# HelpDuinoShiledV1.net
KiCad netlist of a schematic drawn in EAGLE
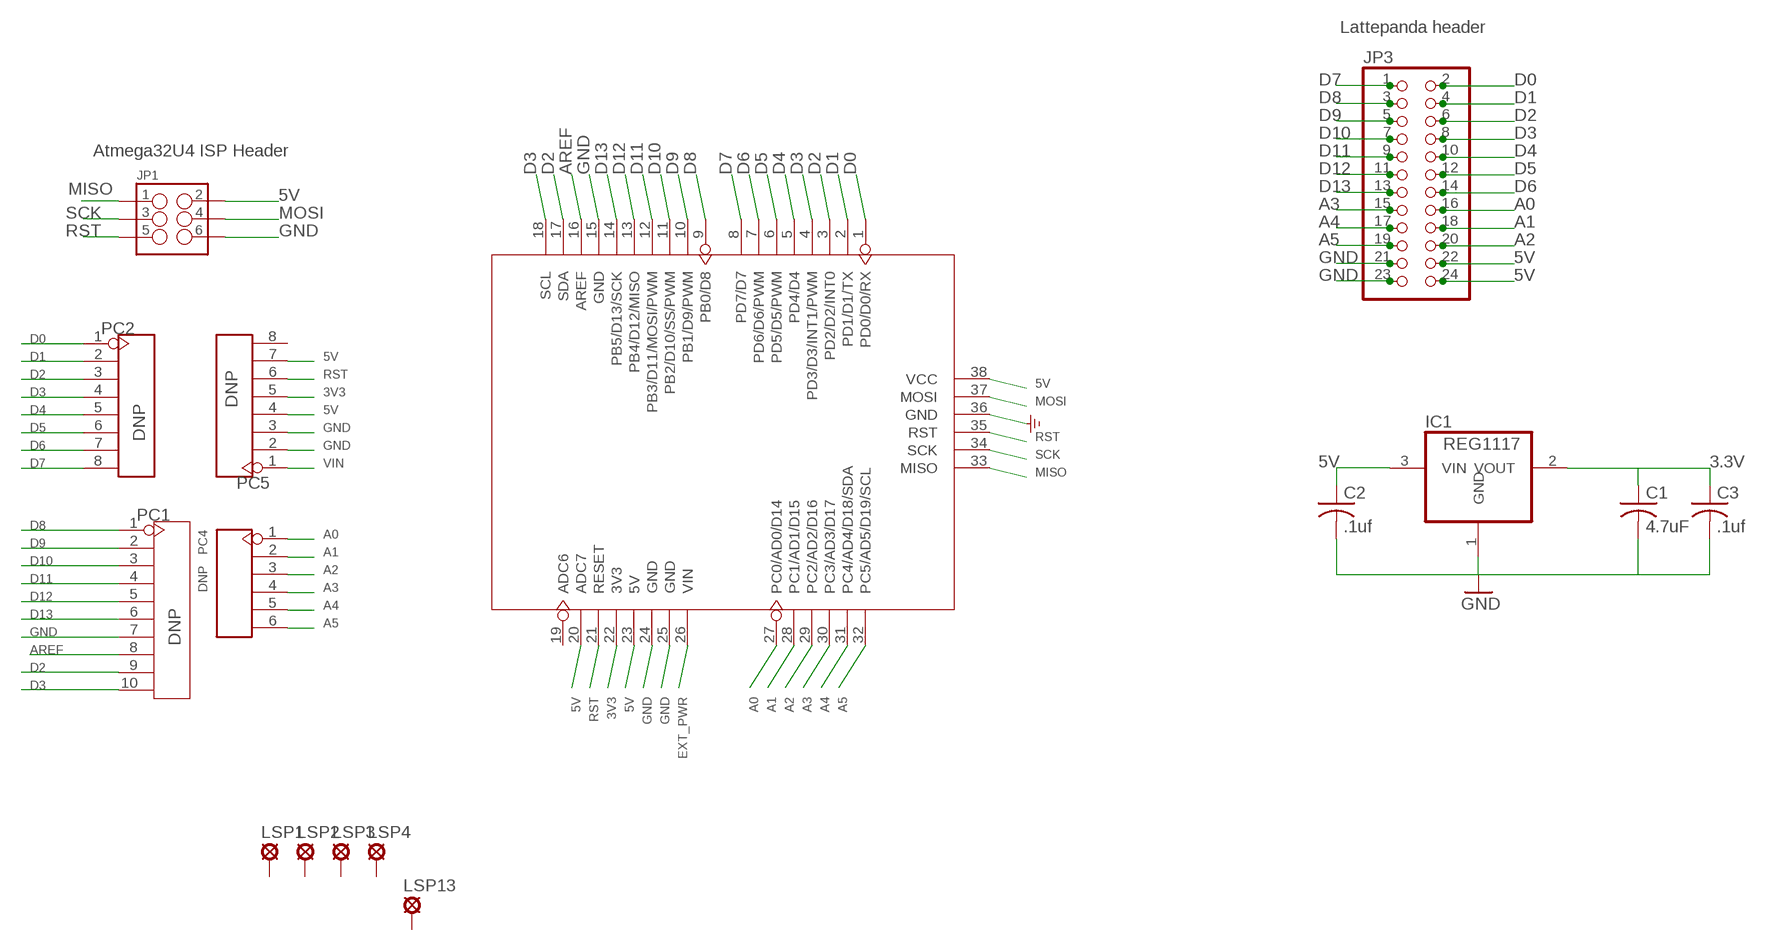
[diagram p0: schematic, sheet 1]

(export (version "E")
  (design (tool "Eeschema 10.0.6"))
  (components
    (comp (ref "C1")
      (value "4.7uF")
      (footprint "eagle-import:C0603K")
      (libsource (lib "eagle-import") (part "C-USC0603K"))
    )
    (comp (ref "C2")
      (value ".1uf")
      (footprint "eagle-import:C0603K")
      (libsource (lib "eagle-import") (part "C-USC0603K"))
    )
    (comp (ref "C3")
      (value ".1uf")
      (footprint "eagle-import:C0603K")
      (libsource (lib "eagle-import") (part "C-USC0603K"))
    )
    (comp (ref "IC1")
      (value "REG1117")
      (footprint "eagle-import:SOT223")
      (libsource (lib "eagle-import") (part "REG1117"))
    )
    (comp (ref "JP1")
      (value "M03X2NO_SILK")
      (footprint "eagle-import:2X3-NS")
      (libsource (lib "eagle-import") (part "M03X2NO_SILK"))
    )
    (comp (ref "JP3")
      (value "PINHD-2X12")
      (footprint "eagle-import:2X12")
      (libsource (lib "eagle-import") (part "PINHD-2X12"))
    )
    (comp (ref "LSP1")
      (value "SE13")
      (footprint "eagle-import:SE13")
      (libsource (lib "eagle-import") (part "SE13"))
    )
    (comp (ref "LSP2")
      (value "SE13")
      (footprint "eagle-import:SE13")
      (libsource (lib "eagle-import") (part "SE13"))
    )
    (comp (ref "LSP3")
      (value "SE13")
      (footprint "eagle-import:SE13")
      (libsource (lib "eagle-import") (part "SE13"))
    )
    (comp (ref "LSP4")
      (value "SE13")
      (footprint "eagle-import:SE13")
      (libsource (lib "eagle-import") (part "SE13"))
    )
    (comp (ref "LSP13")
      (value "SE13")
      (footprint "eagle-import:SE13")
      (libsource (lib "eagle-import") (part "SE13"))
    )
    (comp (ref "PC1")
      (value "DNP")
      (footprint "eagle-import:10P-2.54")
      (libsource (lib "eagle-import") (part "HEADER-10P-2.54"))
    )
    (comp (ref "PC2")
      (value "DNP")
      (footprint "eagle-import:8P-2.54")
      (libsource (lib "eagle-import") (part "HEADER-8P-2.54"))
    )
    (comp (ref "PC4")
      (value "DNP")
      (footprint "eagle-import:6P-2.54-65_35MIL")
      (libsource (lib "eagle-import") (part "HEADER-6P-65/35MIL"))
    )
    (comp (ref "PC5")
      (value "DNP")
      (footprint "eagle-import:8P-2.54")
      (libsource (lib "eagle-import") (part "HEADER-8P-2.54"))
    )
    (comp (ref "U1")
      (value "ARDUINO-38PWITH/-SILK")
      (footprint "eagle-import:ARDUINO-38P-WITH_-SILK-500519002")
      (libsource (lib "eagle-import") (part "ARDUINO-38PWITH/-SILK"))
    )
  )
  (nets
    (net (code "1") (name "/3.3V") (class "Default")
      (node (ref "C1") (pin "1") (pinfunction "1_1") (pintype "passive"))
      (node (ref "C3") (pin "1") (pinfunction "1_1") (pintype "passive"))
      (node (ref "IC1") (pin "2") (pinfunction "VOUT_2") (pintype "output"))
    )
    (net (code "2") (name "/3V3") (class "Default")
      (node (ref "PC5") (pin "5") (pinfunction "5_5") (pintype "bidirectional"))
      (node (ref "U1") (pin "22") (pinfunction "3V3_22") (pintype "bidirectional"))
    )
    (net (code "3") (name "/5V") (class "Default")
      (node (ref "C2") (pin "1") (pinfunction "1_1") (pintype "passive"))
      (node (ref "IC1") (pin "3") (pinfunction "VIN_3") (pintype "input"))
      (node (ref "JP1") (pin "2") (pinfunction "2_2") (pintype "bidirectional"))
      (node (ref "JP3") (pin "22") (pinfunction "22_22") (pintype "passive"))
      (node (ref "JP3") (pin "24") (pinfunction "24_24") (pintype "passive"))
      (node (ref "PC5") (pin "4") (pinfunction "4_4") (pintype "bidirectional"))
      (node (ref "PC5") (pin "7") (pinfunction "7_7") (pintype "bidirectional"))
      (node (ref "U1") (pin "20") (pinfunction "ADC7_20") (pintype "bidirectional"))
      (node (ref "U1") (pin "23") (pinfunction "5V_23") (pintype "bidirectional"))
      (node (ref "U1") (pin "38") (pinfunction "VCC_38") (pintype "bidirectional"))
    )
    (net (code "4") (name "/A0") (class "Default")
      (node (ref "JP3") (pin "16") (pinfunction "16_16") (pintype "passive"))
      (node (ref "PC4") (pin "1") (pinfunction "1_1") (pintype "bidirectional"))
      (node (ref "U1") (pin "27") (pinfunction "PC0/AD0/D14_27") (pintype "bidirectional"))
    )
    (net (code "5") (name "/A1") (class "Default")
      (node (ref "JP3") (pin "18") (pinfunction "18_18") (pintype "passive"))
      (node (ref "PC4") (pin "2") (pinfunction "2_2") (pintype "bidirectional"))
      (node (ref "U1") (pin "28") (pinfunction "PC1/AD1/D15_28") (pintype "bidirectional"))
    )
    (net (code "6") (name "/A2") (class "Default")
      (node (ref "JP3") (pin "20") (pinfunction "20_20") (pintype "passive"))
      (node (ref "PC4") (pin "3") (pinfunction "3_3") (pintype "bidirectional"))
      (node (ref "U1") (pin "29") (pinfunction "PC2/AD2/D16_29") (pintype "bidirectional"))
    )
    (net (code "7") (name "/A3") (class "Default")
      (node (ref "JP3") (pin "15") (pinfunction "15_15") (pintype "passive"))
      (node (ref "PC4") (pin "4") (pinfunction "4_4") (pintype "bidirectional"))
      (node (ref "U1") (pin "30") (pinfunction "PC3/AD3/D17_30") (pintype "bidirectional"))
    )
    (net (code "8") (name "/A4") (class "Default")
      (node (ref "JP3") (pin "17") (pinfunction "17_17") (pintype "passive"))
      (node (ref "PC4") (pin "5") (pinfunction "5_5") (pintype "bidirectional"))
      (node (ref "U1") (pin "31") (pinfunction "PC4/AD4/D18/SDA_31") (pintype "bidirectional"))
    )
    (net (code "9") (name "/A5") (class "Default")
      (node (ref "JP3") (pin "19") (pinfunction "19_19") (pintype "passive"))
      (node (ref "PC4") (pin "6") (pinfunction "6_6") (pintype "bidirectional"))
      (node (ref "U1") (pin "32") (pinfunction "PC5/AD5/D19/SCL_32") (pintype "bidirectional"))
    )
    (net (code "10") (name "/AREF") (class "Default")
      (node (ref "PC1") (pin "8") (pinfunction "8_8") (pintype "bidirectional"))
      (node (ref "U1") (pin "16") (pinfunction "AREF_16") (pintype "bidirectional"))
    )
    (net (code "11") (name "/D0") (class "Default")
      (node (ref "JP3") (pin "2") (pinfunction "2_2") (pintype "passive"))
      (node (ref "PC2") (pin "1") (pinfunction "1_1") (pintype "bidirectional"))
      (node (ref "U1") (pin "1") (pinfunction "PD0/D0/RX_1") (pintype "bidirectional"))
    )
    (net (code "12") (name "/D1") (class "Default")
      (node (ref "JP3") (pin "4") (pinfunction "4_4") (pintype "passive"))
      (node (ref "PC2") (pin "2") (pinfunction "2_2") (pintype "bidirectional"))
      (node (ref "U1") (pin "2") (pinfunction "PD1/D1/TX_2") (pintype "bidirectional"))
    )
    (net (code "13") (name "/D2") (class "Default")
      (node (ref "JP3") (pin "6") (pinfunction "6_6") (pintype "passive"))
      (node (ref "PC1") (pin "9") (pinfunction "9_9") (pintype "bidirectional"))
      (node (ref "PC2") (pin "3") (pinfunction "3_3") (pintype "bidirectional"))
      (node (ref "U1") (pin "17") (pinfunction "SDA_17") (pintype "bidirectional"))
      (node (ref "U1") (pin "3") (pinfunction "PD2/D2/INT0_3") (pintype "bidirectional"))
    )
    (net (code "14") (name "/D3") (class "Default")
      (node (ref "JP3") (pin "8") (pinfunction "8_8") (pintype "passive"))
      (node (ref "PC1") (pin "10") (pinfunction "10_10") (pintype "bidirectional"))
      (node (ref "PC2") (pin "4") (pinfunction "4_4") (pintype "bidirectional"))
      (node (ref "U1") (pin "18") (pinfunction "SCL_18") (pintype "bidirectional"))
      (node (ref "U1") (pin "4") (pinfunction "PD3/D3/INT1/PWM_4") (pintype "bidirectional"))
    )
    (net (code "15") (name "/D4") (class "Default")
      (node (ref "JP3") (pin "10") (pinfunction "10_10") (pintype "passive"))
      (node (ref "PC2") (pin "5") (pinfunction "5_5") (pintype "bidirectional"))
      (node (ref "U1") (pin "5") (pinfunction "PD4/D4_5") (pintype "bidirectional"))
    )
    (net (code "16") (name "/D5") (class "Default")
      (node (ref "JP3") (pin "12") (pinfunction "12_12") (pintype "passive"))
      (node (ref "PC2") (pin "6") (pinfunction "6_6") (pintype "bidirectional"))
      (node (ref "U1") (pin "6") (pinfunction "PD5/D5/PWM_6") (pintype "bidirectional"))
    )
    (net (code "17") (name "/D6") (class "Default")
      (node (ref "JP3") (pin "14") (pinfunction "14_14") (pintype "passive"))
      (node (ref "PC2") (pin "7") (pinfunction "7_7") (pintype "bidirectional"))
      (node (ref "U1") (pin "7") (pinfunction "PD6/D6/PWM_7") (pintype "bidirectional"))
    )
    (net (code "18") (name "/D7") (class "Default")
      (node (ref "JP3") (pin "1") (pinfunction "1_1") (pintype "passive"))
      (node (ref "PC2") (pin "8") (pinfunction "8_8") (pintype "bidirectional"))
      (node (ref "U1") (pin "8") (pinfunction "PD7/D7_8") (pintype "bidirectional"))
    )
    (net (code "19") (name "/D8") (class "Default")
      (node (ref "JP3") (pin "3") (pinfunction "3_3") (pintype "passive"))
      (node (ref "PC1") (pin "1") (pinfunction "1_1") (pintype "bidirectional"))
      (node (ref "U1") (pin "9") (pinfunction "PB0/D8_9") (pintype "bidirectional"))
    )
    (net (code "20") (name "/D9") (class "Default")
      (node (ref "JP3") (pin "5") (pinfunction "5_5") (pintype "passive"))
      (node (ref "PC1") (pin "2") (pinfunction "2_2") (pintype "bidirectional"))
      (node (ref "U1") (pin "10") (pinfunction "PB1/D9/PWM_10") (pintype "bidirectional"))
    )
    (net (code "21") (name "/D10") (class "Default")
      (node (ref "JP3") (pin "7") (pinfunction "7_7") (pintype "passive"))
      (node (ref "PC1") (pin "3") (pinfunction "3_3") (pintype "bidirectional"))
      (node (ref "U1") (pin "11") (pinfunction "PB2/D10/SS/PWM_11") (pintype "bidirectional"))
    )
    (net (code "22") (name "/D11") (class "Default")
      (node (ref "JP3") (pin "9") (pinfunction "9_9") (pintype "passive"))
      (node (ref "PC1") (pin "4") (pinfunction "4_4") (pintype "bidirectional"))
      (node (ref "U1") (pin "12") (pinfunction "PB3/D11/MOSI/PWM_12") (pintype "bidirectional"))
    )
    (net (code "23") (name "/D12") (class "Default")
      (node (ref "JP3") (pin "11") (pinfunction "11_11") (pintype "passive"))
      (node (ref "PC1") (pin "5") (pinfunction "5_5") (pintype "bidirectional"))
      (node (ref "U1") (pin "13") (pinfunction "PB4/D12/MISO_13") (pintype "bidirectional"))
    )
    (net (code "24") (name "/D13") (class "Default")
      (node (ref "JP3") (pin "13") (pinfunction "13_13") (pintype "passive"))
      (node (ref "PC1") (pin "6") (pinfunction "6_6") (pintype "bidirectional"))
      (node (ref "U1") (pin "14") (pinfunction "PB5/D13/SCK_14") (pintype "bidirectional"))
    )
    (net (code "25") (name "/EXT_PWR") (class "Default")
      (node (ref "U1") (pin "26") (pinfunction "VIN_26") (pintype "bidirectional"))
    )
    (net (code "26") (name "/MISO") (class "Default")
      (node (ref "JP1") (pin "1") (pinfunction "1_1") (pintype "bidirectional"))
      (node (ref "U1") (pin "33") (pinfunction "MISO_33") (pintype "bidirectional"))
    )
    (net (code "27") (name "/MOSI") (class "Default")
      (node (ref "JP1") (pin "4") (pinfunction "4_4") (pintype "bidirectional"))
      (node (ref "U1") (pin "37") (pinfunction "MOSI_37") (pintype "bidirectional"))
    )
    (net (code "28") (name "/RST") (class "Default")
      (node (ref "JP1") (pin "5") (pinfunction "5_5") (pintype "bidirectional"))
      (node (ref "PC5") (pin "6") (pinfunction "6_6") (pintype "bidirectional"))
      (node (ref "U1") (pin "21") (pinfunction "RESET_21") (pintype "bidirectional"))
      (node (ref "U1") (pin "35") (pinfunction "RST_35") (pintype "bidirectional"))
    )
    (net (code "29") (name "/SCK") (class "Default")
      (node (ref "JP1") (pin "3") (pinfunction "3_3") (pintype "bidirectional"))
      (node (ref "U1") (pin "34") (pinfunction "SCK_34") (pintype "bidirectional"))
    )
    (net (code "30") (name "/VIN") (class "Default")
      (node (ref "PC5") (pin "1") (pinfunction "1_1") (pintype "bidirectional"))
    )
    (net (code "31") (name "GND") (class "Default")
      (node (ref "C1") (pin "2") (pinfunction "2_2") (pintype "passive"))
      (node (ref "C2") (pin "2") (pinfunction "2_2") (pintype "passive"))
      (node (ref "C3") (pin "2") (pinfunction "2_2") (pintype "passive"))
      (node (ref "IC1") (pin "1") (pinfunction "GND_1") (pintype "power_in"))
      (node (ref "JP1") (pin "6") (pinfunction "6_6") (pintype "bidirectional"))
      (node (ref "JP3") (pin "21") (pinfunction "21_21") (pintype "passive"))
      (node (ref "JP3") (pin "23") (pinfunction "23_23") (pintype "passive"))
      (node (ref "PC1") (pin "7") (pinfunction "7_7") (pintype "bidirectional"))
      (node (ref "PC5") (pin "2") (pinfunction "2_2") (pintype "bidirectional"))
      (node (ref "PC5") (pin "3") (pinfunction "3_3") (pintype "bidirectional"))
      (node (ref "U1") (pin "15") (pinfunction "GND_15") (pintype "bidirectional"))
      (node (ref "U1") (pin "24") (pinfunction "GND_24") (pintype "bidirectional"))
      (node (ref "U1") (pin "25") (pinfunction "GND_25") (pintype "bidirectional"))
      (node (ref "U1") (pin "36") (pinfunction "GND_36") (pintype "bidirectional"))
    )
    (net (code "32") (name "unconnected-(LSP1-PadMP)") (class "Default")
      (node (ref "LSP1") (pin "MP") (pinfunction "MP_MP") (pintype "passive"))
    )
    (net (code "33") (name "unconnected-(LSP2-PadMP)") (class "Default")
      (node (ref "LSP2") (pin "MP") (pinfunction "MP_MP") (pintype "passive"))
    )
    (net (code "34") (name "unconnected-(LSP3-PadMP)") (class "Default")
      (node (ref "LSP3") (pin "MP") (pinfunction "MP_MP") (pintype "passive"))
    )
    (net (code "35") (name "unconnected-(LSP4-PadMP)") (class "Default")
      (node (ref "LSP4") (pin "MP") (pinfunction "MP_MP") (pintype "passive"))
    )
    (net (code "36") (name "unconnected-(LSP13-PadMP)") (class "Default")
      (node (ref "LSP13") (pin "MP") (pinfunction "MP_MP") (pintype "passive"))
    )
    (net (code "37") (name "unconnected-(PC5-Pad8)") (class "Default")
      (node (ref "PC5") (pin "8") (pinfunction "8_8") (pintype "bidirectional"))
    )
    (net (code "38") (name "unconnected-(U1-ADC6-Pad19)") (class "Default")
      (node (ref "U1") (pin "19") (pinfunction "ADC6_19") (pintype "bidirectional"))
    )
  )
)
